# lightswitchx1_triac.net
KiCad netlist of a schematic drawn in EAGLE
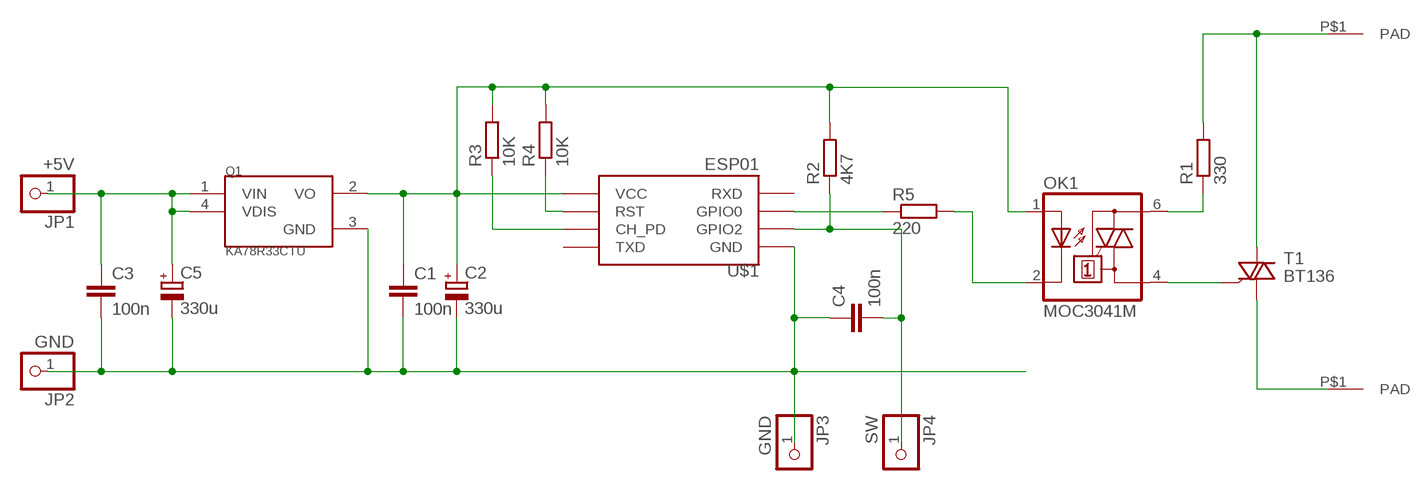
[diagram p0: schematic, sheet 1]

(export (version "E")
  (design (tool "Eeschema 10.0.6"))
  (components
    (comp (ref "C1")
      (value "100n")
      (footprint "eagle-import:C025-030X050")
      (libsource (lib "eagle-import") (part "C-EU025-030X050"))
    )
    (comp (ref "C2")
      (value "330u")
      (footprint "eagle-import:E2-5")
      (libsource (lib "eagle-import") (part "CPOL-EUE2-5"))
    )
    (comp (ref "C3")
      (value "100n")
      (footprint "eagle-import:C025-030X050")
      (libsource (lib "eagle-import") (part "C-EU025-030X050"))
    )
    (comp (ref "C4")
      (value "100n")
      (footprint "eagle-import:C025-030X050")
      (libsource (lib "eagle-import") (part "C-EU025-030X050"))
    )
    (comp (ref "C5")
      (value "330u")
      (footprint "eagle-import:E2-5")
      (libsource (lib "eagle-import") (part "CPOL-EUE2-5"))
    )
    (comp (ref "JP1")
      (value "+5V")
      (footprint "eagle-import:1X01")
      (libsource (lib "eagle-import") (part "PINHD-1X1"))
    )
    (comp (ref "JP2")
      (value "GND")
      (footprint "eagle-import:1X01")
      (libsource (lib "eagle-import") (part "PINHD-1X1"))
    )
    (comp (ref "JP3")
      (value "GND")
      (footprint "eagle-import:1X01")
      (libsource (lib "eagle-import") (part "PINHD-1X1"))
    )
    (comp (ref "JP4")
      (value "SW")
      (footprint "eagle-import:1X01")
      (libsource (lib "eagle-import") (part "PINHD-1X1"))
    )
    (comp (ref "OK1")
      (value "MOC3041M")
      (footprint "eagle-import:DIL06")
      (fields (field (name "MF") "FAIRCHILD SEMICONDUCTOR"))
      (libsource (lib "eagle-import") (part "MOC3041M"))
    )
    (comp (ref "Q1")
      (value "KA78R33CTU")
      (footprint "eagle-import:TO-220-4")
      (fields (field (name "MF") "Fairchild Semiconductor"))
      (libsource (lib "eagle-import") (part "KA78R33CTU"))
    )
    (comp (ref "R1")
      (value "330")
      (footprint "eagle-import:0207_7")
      (libsource (lib "eagle-import") (part "R-EU_0207/7"))
    )
    (comp (ref "R2")
      (value "4K7")
      (footprint "eagle-import:0207_10")
      (libsource (lib "eagle-import") (part "R-EU_0207/10"))
    )
    (comp (ref "R3")
      (value "10K")
      (footprint "eagle-import:0207_10")
      (libsource (lib "eagle-import") (part "R-EU_0207/10"))
    )
    (comp (ref "R4")
      (value "10K")
      (footprint "eagle-import:0207_10")
      (libsource (lib "eagle-import") (part "R-EU_0207/10"))
    )
    (comp (ref "R5")
      (value "220")
      (footprint "eagle-import:0207_7")
      (libsource (lib "eagle-import") (part "R-EU_0207/7"))
    )
    (comp (ref "T1")
      (value "BT136")
      (footprint "eagle-import:TO220AB")
      (libsource (lib "eagle-import") (part "BT136"))
    )
    (comp (ref "U$1")
      (value "ESP01")
      (footprint "eagle-import:ESP01")
      (libsource (lib "eagle-import") (part "ESP01"))
    )
    (comp (ref "U$4")
      (value "PAD")
      (footprint "eagle-import:PAD")
      (libsource (lib "eagle-import") (part "PAD"))
    )
    (comp (ref "U$5")
      (value "PAD")
      (footprint "eagle-import:PAD")
      (libsource (lib "eagle-import") (part "PAD"))
    )
  )
  (nets
    (net (code "1") (name "Net-(C4-Pad2)") (class "Default")
      (node (ref "C4") (pin "2") (pinfunction "2_2") (pintype "passive"))
      (node (ref "JP4") (pin "1") (pinfunction "1_1") (pintype "passive"))
      (node (ref "R2") (pin "1") (pinfunction "1_1") (pintype "passive"))
      (node (ref "U$1") (pin "GPIO2") (pinfunction "GPIO2_GPIO2") (pintype "bidirectional"))
    )
    (net (code "2") (name "Net-(OK1-A)") (class "Default")
      (node (ref "C1") (pin "1") (pinfunction "1_1") (pintype "passive"))
      (node (ref "C2") (pin "+") (pinfunction "+_+") (pintype "passive"))
      (node (ref "OK1") (pin "1") (pinfunction "A_1") (pintype "passive"))
      (node (ref "Q1") (pin "2") (pinfunction "VO_2") (pintype "output"))
      (node (ref "R2") (pin "2") (pinfunction "2_2") (pintype "passive"))
      (node (ref "R3") (pin "2") (pinfunction "2_2") (pintype "passive"))
      (node (ref "R4") (pin "2") (pinfunction "2_2") (pintype "passive"))
      (node (ref "U$1") (pin "VCC") (pinfunction "VCC_VCC") (pintype "bidirectional"))
    )
    (net (code "3") (name "Net-(OK1-A1)") (class "Default")
      (node (ref "OK1") (pin "4") (pinfunction "A1_4") (pintype "passive"))
      (node (ref "T1") (pin "3") (pinfunction "G_3") (pintype "passive"))
    )
    (net (code "4") (name "Net-(OK1-A2)") (class "Default")
      (node (ref "OK1") (pin "6") (pinfunction "A2_6") (pintype "passive"))
      (node (ref "R1") (pin "1") (pinfunction "1_1") (pintype "passive"))
    )
    (net (code "5") (name "Net-(OK1-C)") (class "Default")
      (node (ref "OK1") (pin "2") (pinfunction "C_2") (pintype "passive"))
      (node (ref "R5") (pin "2") (pinfunction "2_2") (pintype "passive"))
    )
    (net (code "6") (name "Net-(Q1-GND)") (class "Default")
      (node (ref "C1") (pin "2") (pinfunction "2_2") (pintype "passive"))
      (node (ref "C2") (pin "-") (pinfunction "-_-") (pintype "passive"))
      (node (ref "C3") (pin "2") (pinfunction "2_2") (pintype "passive"))
      (node (ref "C4") (pin "1") (pinfunction "1_1") (pintype "passive"))
      (node (ref "C5") (pin "-") (pinfunction "-_-") (pintype "passive"))
      (node (ref "JP2") (pin "1") (pinfunction "1_1") (pintype "passive"))
      (node (ref "JP3") (pin "1") (pinfunction "1_1") (pintype "passive"))
      (node (ref "Q1") (pin "3") (pinfunction "GND_3") (pintype "passive"))
      (node (ref "U$1") (pin "GND") (pinfunction "GND_GND") (pintype "bidirectional"))
    )
    (net (code "7") (name "Net-(Q1-VDIS)") (class "Default")
      (node (ref "C3") (pin "1") (pinfunction "1_1") (pintype "passive"))
      (node (ref "C5") (pin "+") (pinfunction "+_+") (pintype "passive"))
      (node (ref "JP1") (pin "1") (pinfunction "1_1") (pintype "passive"))
      (node (ref "Q1") (pin "1") (pinfunction "VIN_1") (pintype "input"))
      (node (ref "Q1") (pin "4") (pinfunction "VDIS_4") (pintype "passive"))
    )
    (net (code "8") (name "Net-(R3-Pad1)") (class "Default")
      (node (ref "R3") (pin "1") (pinfunction "1_1") (pintype "passive"))
      (node (ref "U$1") (pin "CH_PD") (pinfunction "CH_PD_CH_PD") (pintype "bidirectional"))
    )
    (net (code "9") (name "Net-(R4-Pad1)") (class "Default")
      (node (ref "R4") (pin "1") (pinfunction "1_1") (pintype "passive"))
      (node (ref "U$1") (pin "RST") (pinfunction "RST_RST") (pintype "bidirectional"))
    )
    (net (code "10") (name "Net-(R5-Pad1)") (class "Default")
      (node (ref "R5") (pin "1") (pinfunction "1_1") (pintype "passive"))
      (node (ref "U$1") (pin "GPIO0") (pinfunction "GPIO0_GPIO0") (pintype "bidirectional"))
    )
    (net (code "11") (name "Net-(T1-A1)") (class "Default")
      (node (ref "T1") (pin "1") (pinfunction "A1_1") (pintype "passive"))
      (node (ref "U$4") (pin "P$1") (pinfunction "PAD_P$1") (pintype "bidirectional"))
    )
    (net (code "12") (name "Net-(T1-A2)") (class "Default")
      (node (ref "R1") (pin "2") (pinfunction "2_2") (pintype "passive"))
      (node (ref "T1") (pin "2") (pinfunction "A2_2") (pintype "passive"))
      (node (ref "U$5") (pin "P$1") (pinfunction "PAD_P$1") (pintype "bidirectional"))
    )
    (net (code "13") (name "unconnected-(U$1-RXD-PadRX)") (class "Default")
      (node (ref "U$1") (pin "RX") (pinfunction "RXD_RX") (pintype "bidirectional"))
    )
    (net (code "14") (name "unconnected-(U$1-TXD-PadTX)") (class "Default")
      (node (ref "U$1") (pin "TX") (pinfunction "TXD_TX") (pintype "bidirectional"))
    )
  )
)
